# MacroStepper_v3_0.net
KiCad netlist of a schematic drawn in EAGLE
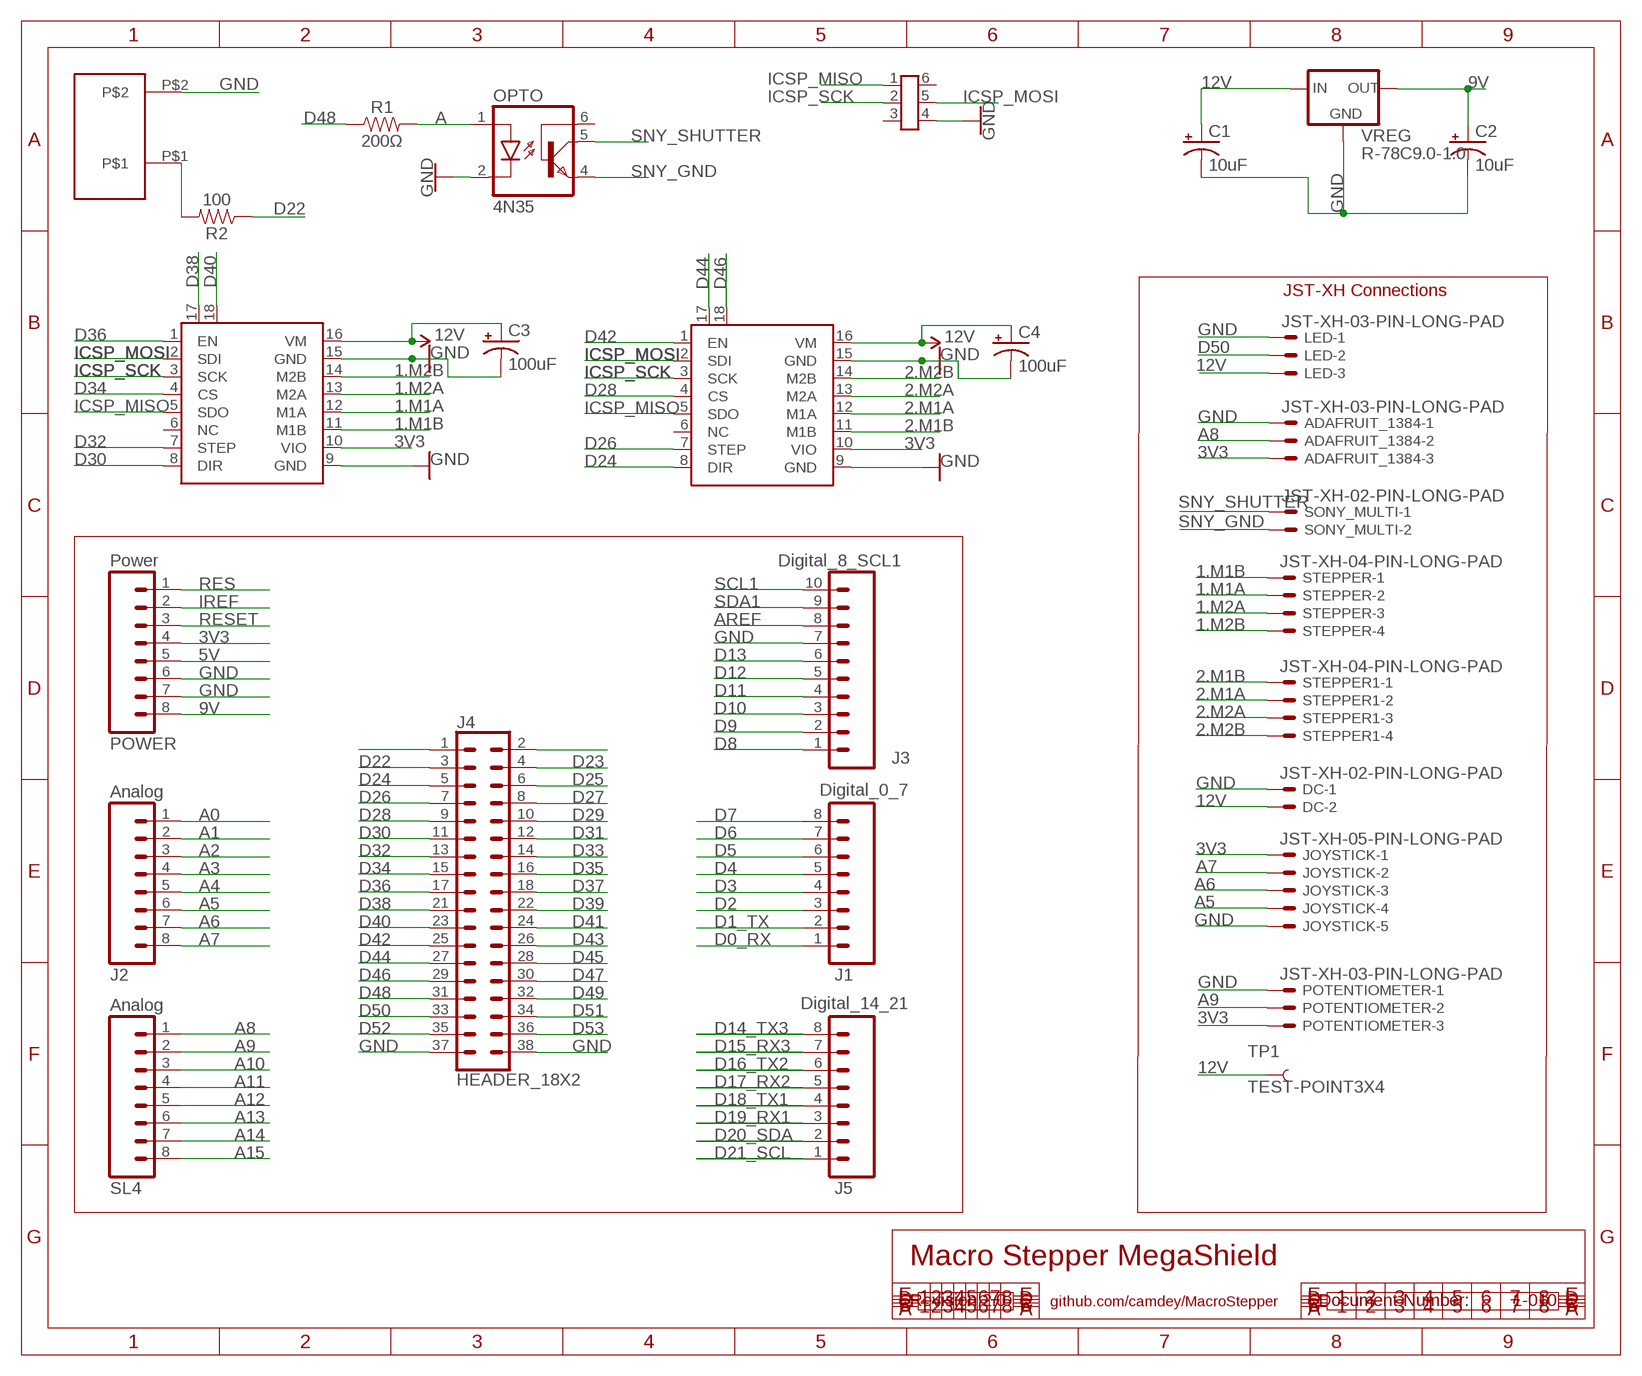
[diagram p0: schematic, sheet 1]

(export (version "E")
  (design (tool "Eeschema 10.0.6"))
  (components
    (comp (ref "ADAFRUIT_1384")
      (value "JST-XH-03-PIN-LONG-PAD")
      (footprint "eagle-import:JST-XH-03-PACKAGE-LONG-PAD")
      (libsource (lib "eagle-import") (part "JST-XH-03-PIN-LONG-PAD"))
    )
    (comp (ref "C1")
      (value "10uF")
      (footprint "eagle-import:CPOL-RADIAL-2.5MM-5MM")
      (libsource (lib "eagle-import") (part "10UF-POLAR-RADIAL-2.5MM-25V-20%"))
    )
    (comp (ref "C2")
      (value "10uF")
      (footprint "eagle-import:CPOL-RADIAL-2.5MM-5MM")
      (libsource (lib "eagle-import") (part "10UF-POLAR-RADIAL-2.5MM-25V-20%"))
    )
    (comp (ref "C3")
      (value "100uF")
      (footprint "eagle-import:CPOL-RADIAL-2.5MM-6.5MM")
      (libsource (lib "eagle-import") (part "100UF-POLAR-RADIAL-2.5MM-25V-20%"))
    )
    (comp (ref "C4")
      (value "100uF")
      (footprint "eagle-import:CPOL-RADIAL-2.5MM-6.5MM")
      (libsource (lib "eagle-import") (part "100UF-POLAR-RADIAL-2.5MM-25V-20%"))
    )
    (comp (ref "DC")
      (value "JST-XH-02-PIN-LONG-PAD")
      (footprint "eagle-import:JST-XH-02-PACKAGE-LONG-PAD")
      (libsource (lib "eagle-import") (part "JST-XH-02-PIN-LONG-PAD"))
    )
    (comp (ref "ICSP")
      (value "MEGA_ICSP")
      (footprint "eagle-import:MEGA_ICSP")
      (libsource (lib "eagle-import") (part "MEGA_ICSP"))
    )
    (comp (ref "J1")
      (value "Digital_0_7")
      (footprint "eagle-import:1X08")
      (libsource (lib "eagle-import") (part "M08"))
    )
    (comp (ref "J2")
      (value "Analog")
      (footprint "eagle-import:1X08")
      (libsource (lib "eagle-import") (part "M08"))
    )
    (comp (ref "J3")
      (value "Digital_8_SCL1")
      (footprint "eagle-import:1X10")
      (libsource (lib "eagle-import") (part "M10{dblquote}"))
    )
    (comp (ref "J4")
      (value "HEADER_18X2")
      (footprint "eagle-import:2X18")
      (libsource (lib "eagle-import") (part "HEADER_18X2"))
    )
    (comp (ref "J5")
      (value "Digital_14_21")
      (footprint "eagle-import:1X08")
      (libsource (lib "eagle-import") (part "M08"))
    )
    (comp (ref "JOYSTICK")
      (value "JST-XH-05-PIN-LONG-PAD")
      (footprint "eagle-import:JST-XH-05-PACKAGE-LONG-PAD")
      (libsource (lib "eagle-import") (part "JST-XH-05-PIN-LONG-PAD"))
    )
    (comp (ref "LED")
      (value "JST-XH-03-PIN-LONG-PAD")
      (footprint "eagle-import:JST-XH-03-PACKAGE-LONG-PAD")
      (libsource (lib "eagle-import") (part "JST-XH-03-PIN-LONG-PAD"))
    )
    (comp (ref "OPTO")
      (value "4N35")
      (footprint "eagle-import:DIL06")
      (fields (field (name "MF") "FAIRCHILD SEMICONDUCTOR"))
      (libsource (lib "eagle-import") (part "4N35"))
    )
    (comp (ref "PIEZO")
      (value "PS1240P02BT")
      (footprint "eagle-import:PS1240P02BT")
      (fields (field (name "MF") "TDK"))
      (libsource (lib "eagle-import") (part "PS1240P02BT"))
    )
    (comp (ref "POTENTIOMETER")
      (value "JST-XH-03-PIN-LONG-PAD")
      (footprint "eagle-import:JST-XH-03-PACKAGE-LONG-PAD")
      (libsource (lib "eagle-import") (part "JST-XH-03-PIN-LONG-PAD"))
    )
    (comp (ref "POWER")
      (value "Power")
      (footprint "eagle-import:1X08")
      (libsource (lib "eagle-import") (part "M08"))
    )
    (comp (ref "R1")
      (value "200Ω")
      (footprint "eagle-import:AXIAL-0.3")
      (libsource (lib "eagle-import") (part "RESISTORAXIAL-0.3"))
    )
    (comp (ref "R2")
      (value "100")
      (footprint "eagle-import:AXIAL-0.3")
      (libsource (lib "eagle-import") (part "100OHM-HORIZ-1/4W-1%"))
    )
    (comp (ref "SL4")
      (value "Analog")
      (footprint "eagle-import:1X08")
      (libsource (lib "eagle-import") (part "M08"))
    )
    (comp (ref "SONY_MULTI")
      (value "JST-XH-02-PIN-LONG-PAD")
      (footprint "eagle-import:JST-XH-02-PACKAGE-LONG-PAD")
      (libsource (lib "eagle-import") (part "JST-XH-02-PIN-LONG-PAD"))
    )
    (comp (ref "STEPPER")
      (value "JST-XH-04-PIN-LONG-PAD")
      (footprint "eagle-import:JST-XH-04-PACKAGE-LONG-PAD")
      (libsource (lib "eagle-import") (part "JST-XH-04-PIN-LONG-PAD"))
    )
    (comp (ref "STEPPER1")
      (value "JST-XH-04-PIN-LONG-PAD")
      (footprint "eagle-import:JST-XH-04-PACKAGE-LONG-PAD")
      (libsource (lib "eagle-import") (part "JST-XH-04-PIN-LONG-PAD"))
    )
    (comp (ref "TMC5160_1")
      (value "TMC2130")
      (footprint "eagle-import:DIL16")
      (libsource (lib "eagle-import") (part "TMC2130"))
    )
    (comp (ref "TMC5160_2")
      (value "TMC2130")
      (footprint "eagle-import:DIL16")
      (libsource (lib "eagle-import") (part "TMC2130"))
    )
    (comp (ref "TP1")
      (value "TEST-POINT3X4")
      (footprint "eagle-import:PAD.03X.04")
      (libsource (lib "eagle-import") (part "TEST-POINT3X4"))
    )
    (comp (ref "VREG")
      (value "R-78C9.0-1.0")
      (footprint "eagle-import:SIP3")
      (fields (field (name "MF") "Recom"))
      (libsource (lib "eagle-import") (part "R-78C-1.09.0"))
    )
  )
  (nets
    (net (code "1") (name "/1.M1A") (class "Default")
      (node (ref "STEPPER") (pin "2") (pinfunction "S_2") (pintype "passive"))
      (node (ref "TMC5160_1") (pin "12") (pinfunction "M1A_12") (pintype "input"))
    )
    (net (code "2") (name "/1.M1B") (class "Default")
      (node (ref "STEPPER") (pin "1") (pinfunction "S_1") (pintype "passive"))
      (node (ref "TMC5160_1") (pin "11") (pinfunction "M1B_11") (pintype "input"))
    )
    (net (code "3") (name "/1.M2A") (class "Default")
      (node (ref "STEPPER") (pin "3") (pinfunction "S_3") (pintype "passive"))
      (node (ref "TMC5160_1") (pin "13") (pinfunction "M2A_13") (pintype "input"))
    )
    (net (code "4") (name "/1.M2B") (class "Default")
      (node (ref "STEPPER") (pin "4") (pinfunction "S_4") (pintype "passive"))
      (node (ref "TMC5160_1") (pin "14") (pinfunction "M2B_14") (pintype "input"))
    )
    (net (code "5") (name "/2.M1A") (class "Default")
      (node (ref "STEPPER1") (pin "2") (pinfunction "S_2") (pintype "passive"))
      (node (ref "TMC5160_2") (pin "12") (pinfunction "M1A_12") (pintype "input"))
    )
    (net (code "6") (name "/2.M1B") (class "Default")
      (node (ref "STEPPER1") (pin "1") (pinfunction "S_1") (pintype "passive"))
      (node (ref "TMC5160_2") (pin "11") (pinfunction "M1B_11") (pintype "input"))
    )
    (net (code "7") (name "/2.M2A") (class "Default")
      (node (ref "STEPPER1") (pin "3") (pinfunction "S_3") (pintype "passive"))
      (node (ref "TMC5160_2") (pin "13") (pinfunction "M2A_13") (pintype "input"))
    )
    (net (code "8") (name "/2.M2B") (class "Default")
      (node (ref "STEPPER1") (pin "4") (pinfunction "S_4") (pintype "passive"))
      (node (ref "TMC5160_2") (pin "14") (pinfunction "M2B_14") (pintype "input"))
    )
    (net (code "9") (name "/3V3") (class "Default")
      (node (ref "ADAFRUIT_1384") (pin "3") (pinfunction "S_3") (pintype "passive"))
      (node (ref "JOYSTICK") (pin "1") (pinfunction "S_1") (pintype "passive"))
      (node (ref "POTENTIOMETER") (pin "3") (pinfunction "S_3") (pintype "passive"))
      (node (ref "POWER") (pin "4") (pinfunction "4_4") (pintype "passive"))
      (node (ref "TMC5160_1") (pin "10") (pinfunction "VIO_10") (pintype "power_in"))
      (node (ref "TMC5160_2") (pin "10") (pinfunction "VIO_10") (pintype "power_in"))
    )
    (net (code "10") (name "/5V") (class "Default")
      (node (ref "POWER") (pin "5") (pinfunction "5_5") (pintype "passive"))
    )
    (net (code "11") (name "/9V") (class "Default")
      (node (ref "C2") (pin "1") (pinfunction "+_1") (pintype "passive"))
      (node (ref "POWER") (pin "8") (pinfunction "8_8") (pintype "passive"))
      (node (ref "VREG") (pin "3") (pinfunction "OUT_3") (pintype "passive"))
    )
    (net (code "12") (name "/A") (class "Default")
      (node (ref "OPTO") (pin "1") (pinfunction "A_1") (pintype "passive"))
      (node (ref "R1") (pin "P$2") (pinfunction "2_P$2") (pintype "passive"))
    )
    (net (code "13") (name "/A0") (class "Default")
      (node (ref "J2") (pin "1") (pinfunction "1_1") (pintype "passive"))
    )
    (net (code "14") (name "/A1") (class "Default")
      (node (ref "J2") (pin "2") (pinfunction "2_2") (pintype "passive"))
    )
    (net (code "15") (name "/A2") (class "Default")
      (node (ref "J2") (pin "3") (pinfunction "3_3") (pintype "passive"))
    )
    (net (code "16") (name "/A3") (class "Default")
      (node (ref "J2") (pin "4") (pinfunction "4_4") (pintype "passive"))
    )
    (net (code "17") (name "/A4") (class "Default")
      (node (ref "J2") (pin "5") (pinfunction "5_5") (pintype "passive"))
    )
    (net (code "18") (name "/A5") (class "Default")
      (node (ref "J2") (pin "6") (pinfunction "6_6") (pintype "passive"))
      (node (ref "JOYSTICK") (pin "4") (pinfunction "S_4") (pintype "passive"))
    )
    (net (code "19") (name "/A6") (class "Default")
      (node (ref "J2") (pin "7") (pinfunction "7_7") (pintype "passive"))
      (node (ref "JOYSTICK") (pin "3") (pinfunction "S_3") (pintype "passive"))
    )
    (net (code "20") (name "/A7") (class "Default")
      (node (ref "J2") (pin "8") (pinfunction "8_8") (pintype "passive"))
      (node (ref "JOYSTICK") (pin "2") (pinfunction "S_2") (pintype "passive"))
    )
    (net (code "21") (name "/A8") (class "Default")
      (node (ref "ADAFRUIT_1384") (pin "2") (pinfunction "S_2") (pintype "passive"))
      (node (ref "SL4") (pin "1") (pinfunction "1_1") (pintype "passive"))
    )
    (net (code "22") (name "/A9") (class "Default")
      (node (ref "POTENTIOMETER") (pin "2") (pinfunction "S_2") (pintype "passive"))
      (node (ref "SL4") (pin "2") (pinfunction "2_2") (pintype "passive"))
    )
    (net (code "23") (name "/A10") (class "Default")
      (node (ref "SL4") (pin "3") (pinfunction "3_3") (pintype "passive"))
    )
    (net (code "24") (name "/A11") (class "Default")
      (node (ref "SL4") (pin "4") (pinfunction "4_4") (pintype "passive"))
    )
    (net (code "25") (name "/A12") (class "Default")
      (node (ref "SL4") (pin "5") (pinfunction "5_5") (pintype "passive"))
    )
    (net (code "26") (name "/A13") (class "Default")
      (node (ref "SL4") (pin "6") (pinfunction "6_6") (pintype "passive"))
    )
    (net (code "27") (name "/A14") (class "Default")
      (node (ref "SL4") (pin "7") (pinfunction "7_7") (pintype "passive"))
    )
    (net (code "28") (name "/A15") (class "Default")
      (node (ref "SL4") (pin "8") (pinfunction "8_8") (pintype "passive"))
    )
    (net (code "29") (name "/AREF") (class "Default")
      (node (ref "J3") (pin "8") (pinfunction "8_8") (pintype "passive"))
    )
    (net (code "30") (name "/D0_RX") (class "Default")
      (node (ref "J1") (pin "1") (pinfunction "1_1") (pintype "passive"))
    )
    (net (code "31") (name "/D1_TX") (class "Default")
      (node (ref "J1") (pin "2") (pinfunction "2_2") (pintype "passive"))
    )
    (net (code "32") (name "/D2") (class "Default")
      (node (ref "J1") (pin "3") (pinfunction "3_3") (pintype "passive"))
    )
    (net (code "33") (name "/D3") (class "Default")
      (node (ref "J1") (pin "4") (pinfunction "4_4") (pintype "passive"))
    )
    (net (code "34") (name "/D4") (class "Default")
      (node (ref "J1") (pin "5") (pinfunction "5_5") (pintype "passive"))
    )
    (net (code "35") (name "/D5") (class "Default")
      (node (ref "J1") (pin "6") (pinfunction "6_6") (pintype "passive"))
    )
    (net (code "36") (name "/D6") (class "Default")
      (node (ref "J1") (pin "7") (pinfunction "7_7") (pintype "passive"))
    )
    (net (code "37") (name "/D7") (class "Default")
      (node (ref "J1") (pin "8") (pinfunction "8_8") (pintype "passive"))
    )
    (net (code "38") (name "/D8") (class "Default")
      (node (ref "J3") (pin "1") (pinfunction "1_1") (pintype "passive"))
    )
    (net (code "39") (name "/D9") (class "Default")
      (node (ref "J3") (pin "2") (pinfunction "2_2") (pintype "passive"))
    )
    (net (code "40") (name "/D10") (class "Default")
      (node (ref "J3") (pin "3") (pinfunction "3_3") (pintype "passive"))
    )
    (net (code "41") (name "/D11") (class "Default")
      (node (ref "J3") (pin "4") (pinfunction "4_4") (pintype "passive"))
    )
    (net (code "42") (name "/D12") (class "Default")
      (node (ref "J3") (pin "5") (pinfunction "5_5") (pintype "passive"))
    )
    (net (code "43") (name "/D13") (class "Default")
      (node (ref "J3") (pin "6") (pinfunction "6_6") (pintype "passive"))
    )
    (net (code "44") (name "/D14_TX3") (class "Default")
      (node (ref "J5") (pin "8") (pinfunction "8_8") (pintype "passive"))
    )
    (net (code "45") (name "/D15_RX3") (class "Default")
      (node (ref "J5") (pin "7") (pinfunction "7_7") (pintype "passive"))
    )
    (net (code "46") (name "/D16_TX2") (class "Default")
      (node (ref "J5") (pin "6") (pinfunction "6_6") (pintype "passive"))
    )
    (net (code "47") (name "/D17_RX2") (class "Default")
      (node (ref "J5") (pin "5") (pinfunction "5_5") (pintype "passive"))
    )
    (net (code "48") (name "/D18_TX1") (class "Default")
      (node (ref "J5") (pin "4") (pinfunction "4_4") (pintype "passive"))
    )
    (net (code "49") (name "/D19_RX1") (class "Default")
      (node (ref "J5") (pin "3") (pinfunction "3_3") (pintype "passive"))
    )
    (net (code "50") (name "/D20_SDA") (class "Default")
      (node (ref "J5") (pin "2") (pinfunction "2_2") (pintype "passive"))
    )
    (net (code "51") (name "/D21_SCL") (class "Default")
      (node (ref "J5") (pin "1") (pinfunction "1_1") (pintype "passive"))
    )
    (net (code "52") (name "/D22") (class "Default")
      (node (ref "J4") (pin "3") (pinfunction "D22_3") (pintype "bidirectional"))
      (node (ref "R2") (pin "P$1") (pinfunction "1_P$1") (pintype "passive"))
    )
    (net (code "53") (name "/D23") (class "Default")
      (node (ref "J4") (pin "4") (pinfunction "D23_4") (pintype "bidirectional"))
    )
    (net (code "54") (name "/D24") (class "Default")
      (node (ref "J4") (pin "5") (pinfunction "D24_5") (pintype "bidirectional"))
      (node (ref "TMC5160_2") (pin "8") (pinfunction "DIR_8") (pintype "input"))
    )
    (net (code "55") (name "/D25") (class "Default")
      (node (ref "J4") (pin "6") (pinfunction "D25_6") (pintype "bidirectional"))
    )
    (net (code "56") (name "/D26") (class "Default")
      (node (ref "J4") (pin "7") (pinfunction "D26_7") (pintype "bidirectional"))
      (node (ref "TMC5160_2") (pin "7") (pinfunction "STEP_7") (pintype "input"))
    )
    (net (code "57") (name "/D27") (class "Default")
      (node (ref "J4") (pin "8") (pinfunction "D27_8") (pintype "bidirectional"))
    )
    (net (code "58") (name "/D28") (class "Default")
      (node (ref "J4") (pin "9") (pinfunction "D28_9") (pintype "bidirectional"))
      (node (ref "TMC5160_2") (pin "4") (pinfunction "CS_4") (pintype "input"))
    )
    (net (code "59") (name "/D29") (class "Default")
      (node (ref "J4") (pin "10") (pinfunction "D29_10") (pintype "bidirectional"))
    )
    (net (code "60") (name "/D30") (class "Default")
      (node (ref "J4") (pin "11") (pinfunction "D30_11") (pintype "bidirectional"))
      (node (ref "TMC5160_1") (pin "8") (pinfunction "DIR_8") (pintype "input"))
    )
    (net (code "61") (name "/D31") (class "Default")
      (node (ref "J4") (pin "12") (pinfunction "D31_12") (pintype "bidirectional"))
    )
    (net (code "62") (name "/D32") (class "Default")
      (node (ref "J4") (pin "13") (pinfunction "D32_13") (pintype "bidirectional"))
      (node (ref "TMC5160_1") (pin "7") (pinfunction "STEP_7") (pintype "input"))
    )
    (net (code "63") (name "/D33") (class "Default")
      (node (ref "J4") (pin "14") (pinfunction "D33_14") (pintype "bidirectional"))
    )
    (net (code "64") (name "/D34") (class "Default")
      (node (ref "J4") (pin "15") (pinfunction "D34_15") (pintype "bidirectional"))
      (node (ref "TMC5160_1") (pin "4") (pinfunction "CS_4") (pintype "input"))
    )
    (net (code "65") (name "/D35") (class "Default")
      (node (ref "J4") (pin "16") (pinfunction "D35_16") (pintype "bidirectional"))
    )
    (net (code "66") (name "/D36") (class "Default")
      (node (ref "J4") (pin "17") (pinfunction "D36_17") (pintype "bidirectional"))
      (node (ref "TMC5160_1") (pin "1") (pinfunction "EN_1") (pintype "input"))
    )
    (net (code "67") (name "/D37") (class "Default")
      (node (ref "J4") (pin "18") (pinfunction "D37_18") (pintype "bidirectional"))
    )
    (net (code "68") (name "/D38") (class "Default")
      (node (ref "J4") (pin "21") (pinfunction "D38_21") (pintype "bidirectional"))
      (node (ref "TMC5160_1") (pin "17") (pinfunction "DIAG0_17") (pintype "output"))
    )
    (net (code "69") (name "/D39") (class "Default")
      (node (ref "J4") (pin "22") (pinfunction "D39_22") (pintype "bidirectional"))
    )
    (net (code "70") (name "/D40") (class "Default")
      (node (ref "J4") (pin "23") (pinfunction "D40_23") (pintype "bidirectional"))
      (node (ref "TMC5160_1") (pin "18") (pinfunction "DIAG1_18") (pintype "output"))
    )
    (net (code "71") (name "/D41") (class "Default")
      (node (ref "J4") (pin "24") (pinfunction "D41_24") (pintype "bidirectional"))
    )
    (net (code "72") (name "/D42") (class "Default")
      (node (ref "J4") (pin "25") (pinfunction "D42_25") (pintype "bidirectional"))
      (node (ref "TMC5160_2") (pin "1") (pinfunction "EN_1") (pintype "input"))
    )
    (net (code "73") (name "/D43") (class "Default")
      (node (ref "J4") (pin "26") (pinfunction "D43_26") (pintype "bidirectional"))
    )
    (net (code "74") (name "/D44") (class "Default")
      (node (ref "J4") (pin "27") (pinfunction "D44_27") (pintype "bidirectional"))
      (node (ref "TMC5160_2") (pin "17") (pinfunction "DIAG0_17") (pintype "output"))
    )
    (net (code "75") (name "/D45") (class "Default")
      (node (ref "J4") (pin "28") (pinfunction "D45_28") (pintype "bidirectional"))
    )
    (net (code "76") (name "/D46") (class "Default")
      (node (ref "J4") (pin "29") (pinfunction "D46_29") (pintype "bidirectional"))
      (node (ref "TMC5160_2") (pin "18") (pinfunction "DIAG1_18") (pintype "output"))
    )
    (net (code "77") (name "/D47") (class "Default")
      (node (ref "J4") (pin "30") (pinfunction "D47_30") (pintype "bidirectional"))
    )
    (net (code "78") (name "/D48") (class "Default")
      (node (ref "J4") (pin "31") (pinfunction "D48_31") (pintype "bidirectional"))
      (node (ref "R1") (pin "P$1") (pinfunction "1_P$1") (pintype "passive"))
    )
    (net (code "79") (name "/D49") (class "Default")
      (node (ref "J4") (pin "32") (pinfunction "D49_32") (pintype "bidirectional"))
    )
    (net (code "80") (name "/D50") (class "Default")
      (node (ref "J4") (pin "33") (pinfunction "D50_33") (pintype "bidirectional"))
      (node (ref "LED") (pin "2") (pinfunction "S_2") (pintype "passive"))
    )
    (net (code "81") (name "/D51") (class "Default")
      (node (ref "J4") (pin "34") (pinfunction "D51_34") (pintype "bidirectional"))
    )
    (net (code "82") (name "/D52") (class "Default")
      (node (ref "J4") (pin "35") (pinfunction "D52_35") (pintype "bidirectional"))
    )
    (net (code "83") (name "/D53") (class "Default")
      (node (ref "J4") (pin "36") (pinfunction "D53_36") (pintype "bidirectional"))
    )
    (net (code "84") (name "/ICSP_MISO") (class "Default")
      (node (ref "ICSP") (pin "1") (pinfunction "MISO_1") (pintype "bidirectional"))
      (node (ref "TMC5160_1") (pin "5") (pinfunction "SDO_5") (pintype "output"))
      (node (ref "TMC5160_2") (pin "5") (pinfunction "SDO_5") (pintype "output"))
    )
    (net (code "85") (name "/ICSP_MOSI") (class "Default")
      (node (ref "ICSP") (pin "5") (pinfunction "MOSI_5") (pintype "bidirectional"))
      (node (ref "TMC5160_1") (pin "2") (pinfunction "SDI_2") (pintype "input"))
      (node (ref "TMC5160_2") (pin "2") (pinfunction "SDI_2") (pintype "input"))
    )
    (net (code "86") (name "/ICSP_SCK") (class "Default")
      (node (ref "ICSP") (pin "2") (pinfunction "SCK_2") (pintype "bidirectional"))
      (node (ref "TMC5160_1") (pin "3") (pinfunction "SCK_3") (pintype "input"))
      (node (ref "TMC5160_2") (pin "3") (pinfunction "SCK_3") (pintype "input"))
    )
    (net (code "87") (name "/IREF") (class "Default")
      (node (ref "POWER") (pin "2") (pinfunction "2_2") (pintype "passive"))
    )
    (net (code "88") (name "/RES") (class "Default")
      (node (ref "POWER") (pin "1") (pinfunction "1_1") (pintype "passive"))
    )
    (net (code "89") (name "/RESET") (class "Default")
      (node (ref "POWER") (pin "3") (pinfunction "3_3") (pintype "passive"))
    )
    (net (code "90") (name "/SCL1") (class "Default")
      (node (ref "J3") (pin "10") (pinfunction "10_10") (pintype "passive"))
    )
    (net (code "91") (name "/SDA1") (class "Default")
      (node (ref "J3") (pin "9") (pinfunction "9_9") (pintype "passive"))
    )
    (net (code "92") (name "/SNY_GND") (class "Default")
      (node (ref "OPTO") (pin "4") (pinfunction "EMI_4") (pintype "passive"))
      (node (ref "SONY_MULTI") (pin "2") (pinfunction "S_2") (pintype "passive"))
    )
    (net (code "93") (name "/SNY_SHUTTER") (class "Default")
      (node (ref "OPTO") (pin "5") (pinfunction "COL_5") (pintype "passive"))
      (node (ref "SONY_MULTI") (pin "1") (pinfunction "S_1") (pintype "passive"))
    )
    (net (code "94") (name "12V") (class "Default")
      (node (ref "C1") (pin "1") (pinfunction "+_1") (pintype "passive"))
      (node (ref "C3") (pin "1") (pinfunction "+_1") (pintype "passive"))
      (node (ref "C4") (pin "1") (pinfunction "+_1") (pintype "passive"))
      (node (ref "DC") (pin "2") (pinfunction "S_2") (pintype "passive"))
      (node (ref "LED") (pin "3") (pinfunction "S_3") (pintype "passive"))
      (node (ref "TMC5160_1") (pin "16") (pinfunction "VM_16") (pintype "power_in"))
      (node (ref "TMC5160_2") (pin "16") (pinfunction "VM_16") (pintype "power_in"))
      (node (ref "TP1") (pin "P$1") (pinfunction "1_P$1") (pintype "bidirectional"))
      (node (ref "VREG") (pin "1") (pinfunction "IN_1") (pintype "input"))
    )
    (net (code "95") (name "GND") (class "Default")
      (node (ref "ADAFRUIT_1384") (pin "1") (pinfunction "S_1") (pintype "passive"))
      (node (ref "C1") (pin "2") (pinfunction "-_2") (pintype "passive"))
      (node (ref "C2") (pin "2") (pinfunction "-_2") (pintype "passive"))
      (node (ref "C3") (pin "2") (pinfunction "-_2") (pintype "passive"))
      (node (ref "C4") (pin "2") (pinfunction "-_2") (pintype "passive"))
      (node (ref "DC") (pin "1") (pinfunction "S_1") (pintype "passive"))
      (node (ref "ICSP") (pin "4") (pinfunction "GND_4") (pintype "power_in"))
      (node (ref "J3") (pin "7") (pinfunction "7_7") (pintype "passive"))
      (node (ref "J4") (pin "37") (pinfunction "GND_37") (pintype "power_in"))
      (node (ref "J4") (pin "38") (pinfunction "GND_38") (pintype "power_in"))
      (node (ref "JOYSTICK") (pin "5") (pinfunction "S_5") (pintype "passive"))
      (node (ref "LED") (pin "1") (pinfunction "S_1") (pintype "passive"))
      (node (ref "OPTO") (pin "2") (pinfunction "C_2") (pintype "passive"))
      (node (ref "PIEZO") (pin "P$2") (pinfunction "P$2_P$2") (pintype "bidirectional"))
      (node (ref "POTENTIOMETER") (pin "1") (pinfunction "S_1") (pintype "passive"))
      (node (ref "POWER") (pin "6") (pinfunction "6_6") (pintype "passive"))
      (node (ref "POWER") (pin "7") (pinfunction "7_7") (pintype "passive"))
      (node (ref "TMC5160_1") (pin "15") (pinfunction "GND_15") (pintype "power_in"))
      (node (ref "TMC5160_1") (pin "9") (pinfunction "GND_9") (pintype "power_in"))
      (node (ref "TMC5160_2") (pin "15") (pinfunction "GND_15") (pintype "power_in"))
      (node (ref "TMC5160_2") (pin "9") (pinfunction "GND_9") (pintype "power_in"))
      (node (ref "VREG") (pin "2") (pinfunction "GND_2") (pintype "input"))
    )
    (net (code "96") (name "Net-(R2-2)") (class "Default")
      (node (ref "PIEZO") (pin "P$1") (pinfunction "P$1_P$1") (pintype "bidirectional"))
      (node (ref "R2") (pin "P$2") (pinfunction "2_P$2") (pintype "passive"))
    )
    (net (code "97") (name "unconnected-(ICSP-5V-Pad6)") (class "Default")
      (node (ref "ICSP") (pin "6") (pinfunction "5V_6") (pintype "no_connect"))
    )
    (net (code "98") (name "unconnected-(ICSP-RST-Pad3)") (class "Default")
      (node (ref "ICSP") (pin "3") (pinfunction "RST_3") (pintype "no_connect"))
    )
    (net (code "99") (name "unconnected-(J4-5V-Pad1)") (class "Default")
      (node (ref "J4") (pin "1") (pinfunction "5V_1") (pintype "power_in"))
    )
    (net (code "100") (name "unconnected-(J4-5V-Pad2)") (class "Default")
      (node (ref "J4") (pin "2") (pinfunction "5V_2") (pintype "power_in"))
    )
    (net (code "101") (name "unconnected-(OPTO-BAS-Pad6)") (class "Default")
      (node (ref "OPTO") (pin "6") (pinfunction "BAS_6") (pintype "passive"))
    )
    (net (code "102") (name "unconnected-(TMC5160_1-NC-Pad6)") (class "Default")
      (node (ref "TMC5160_1") (pin "6") (pinfunction "NC_6") (pintype "no_connect"))
    )
    (net (code "103") (name "unconnected-(TMC5160_2-NC-Pad6)") (class "Default")
      (node (ref "TMC5160_2") (pin "6") (pinfunction "NC_6") (pintype "no_connect"))
    )
  )
)
